# Sheet1.net
KiCad netlist of a schematic drawn in Altium Designer
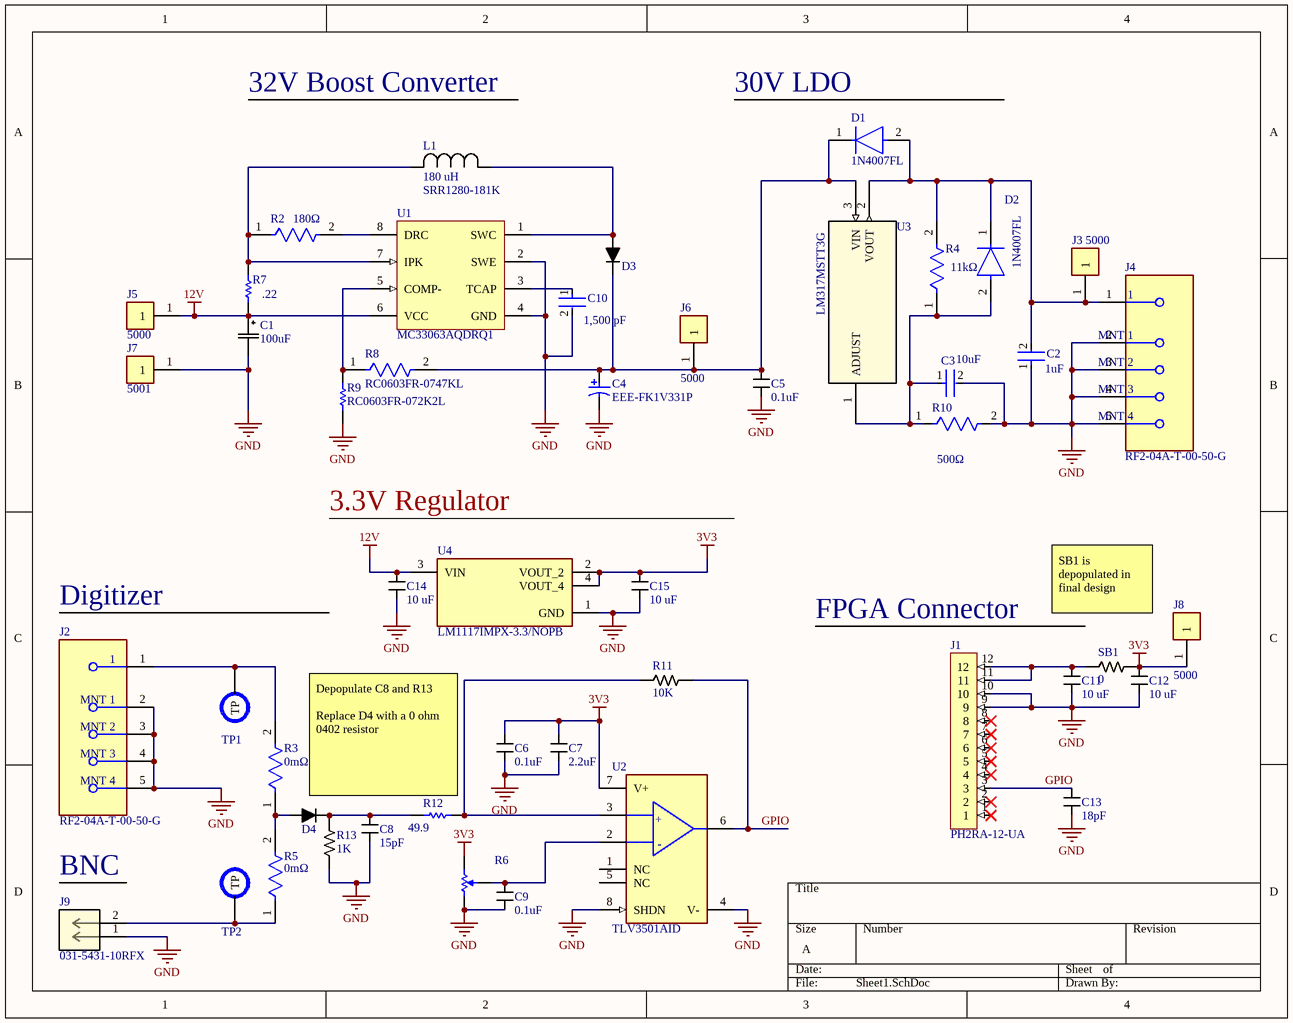
[diagram p0: Sheet1.SchDoc]

(export (version "E")
  (design (tool "Eeschema 10.0.6"))
  (components
    (comp (ref "C1")
      (value "100uF")
      (footprint "PCAP_8x5.4-ELECT_NCA")
      (description "100 µF 35 V Aluminum Electrolytic Capacitors Radial, Can - SMD 1000 Hrs")
      (fields
        (field (name "MANUFACTURER_PART_NUMBER") "UCB1V0R1MCL1GS")
        (field (name "Comment") "100uF electrolytic 35 V")
        (field (name "COPYRIGHT") "Copyright (C) 2022 Ultra Librarian. All rights reserved.")
        (field (name "MADE BY") "Tyson Nguyen")
      )
      (libsource (lib "Capacitors") (part "CAP ALUM 100UF 20% 35V SMD"))
    )
    (comp (ref "C2")
      (value "UMK107BJ105KA-T")
      (footprint "FP-0603-L_1_6_0_1-W_0_8_0-IPC_A")
      (description "None")
      (fields (field (name "TOLERANCE") "10%") (field (name "CAPACITANCE") "1uF"))
      (libsource (lib "Altium Content Vault") (part "02cd4be3c70576c341d710602a673aa"))
    )
    (comp (ref "C3")
      (value "GRM188R6YA106MA73D")
      (footprint "FP-GRM188-0_2-IPC_C")
      (description "Chip Multilayer Ceramic Capacitors for General Purpose, 0603, 10uF, X5R, 15%, 20%, 35V")
      (fields (field (name "CAPACITANCE") "10uF") (field (name "TOLERANCE") "20%"))
      (libsource (lib "Altium Content Vault") (part "11868f565c42a9108669ba33697ecf6"))
    )
    (comp (ref "C4")
      (value "EEE-FK1V331P")
      (footprint "PNSC-EEE-FK1V331P_L")
      (description "Aluminum Electrolytic Capacitor, 330 uF, 35 V, -55 to 105 degC, 2-Pin CAPAE, RoHS, Tape and Reel")
      (fields (field (name "MANUFACTURER") "Panasonic"))
      (libsource (lib "Altium Content Vault") (part "CAP-P-2"))
    )
    (comp (ref "C5")
      (value "0.1uF")
      (footprint "CAPACITOR_0805")
      (description "Cap 100nF 50V +/-10%\r\nCeramic 0805")
      (fields
        (field (name "TOLERANCE") "+/- 10%")
        (field (name "VOLTAGE") "50V")
        (field (name "MADE BY") "Robert Pafford")
      )
      (libsource (lib "Capacitors") (part "CAPACITOR_0.1uF_0805"))
    )
    (comp (ref "C6")
      (value "0.1uF")
      (footprint "CAPACITOR_0603")
      (description "Cap 100nF 25V +/-10%\r\nCeramic 0603")
      (fields
        (field (name "TOLERANCE") "+/- 10%")
        (field (name "VOLTAGE") "6.3V")
        (field (name "MADE BY") "Flip B")
      )
      (libsource (lib "Capacitors") (part "CAPACITOR_0.1uF_0603_25V"))
    )
    (comp (ref "C7")
      (value "2.2uF")
      (footprint "CAPACITOR_0402")
      (description "Cap 2.2uF 35V +/-10%\r\nCeramic 0402")
      (fields
        (field (name "TOLERANCE") "+/- 10%")
        (field (name "VOLTAGE") "35V")
        (field (name "MADE BY") "Flip B")
      )
      (libsource (lib "Capacitors") (part "CAPACITOR_2.2uF_0402"))
    )
    (comp (ref "C8")
      (value "15pF")
      (footprint "CAPACITOR_0402")
      (description "CAP CER 15PF 50V C0G/NP0 0402")
      (fields
        (field (name "TOLERANCE") "+/- 5%")
        (field (name "VOLTAGE") "50V")
        (field (name "MADE BY") "Robert Pafford")
      )
      (libsource (lib "Capacitors") (part "CAPACITOR_0.000015uF_0402"))
    )
    (comp (ref "C9")
      (value "0.1uF")
      (footprint "CAPACITOR_0603")
      (description "Cap 100nF 25V +/-10%\r\nCeramic 0603")
      (fields
        (field (name "TOLERANCE") "+/- 10%")
        (field (name "VOLTAGE") "6.3V")
        (field (name "MADE BY") "Flip B")
      )
      (libsource (lib "Capacitors") (part "CAPACITOR_0.1uF_0603_25V"))
    )
    (comp (ref "C10")
      (value "1,500 pF")
      (footprint "FP-C0603C-CF-MFG")
      (description "CAP CER 1500PF 100V NP0 0603")
      (fields (field (name "MANUFACTURER") "KEMET") (field (name "TOLERANCE") "0.01"))
      (libsource (lib "Altium Content Vault") (part "b4654b650e69147ec39a6b967a45e02"))
    )
    (comp (ref "C11")
      (value "10uF Ceramic 6.3V")
      (footprint "CAPACITOR_0603")
      (description "Cap 10uF 6.3V +/-20%\r\nCeramic 0603")
      (fields
        (field (name "TOLERANCE") "+/- 20%")
        (field (name "VOLTAGE") "6.3V")
        (field (name "VALUE (UF)") "10 uF")
        (field (name "MADE BY") "Flip B")
      )
      (libsource (lib "Capacitors") (part "CAPACITOR_10uF_0603"))
    )
    (comp (ref "C12")
      (value "10uF Ceramic 6.3V")
      (footprint "CAPACITOR_0603")
      (description "Cap 10uF 6.3V +/-20%\r\nCeramic 0603")
      (fields
        (field (name "TOLERANCE") "+/- 20%")
        (field (name "VOLTAGE") "6.3V")
        (field (name "VALUE (UF)") "10 uF")
        (field (name "MADE BY") "Flip B")
      )
      (libsource (lib "Capacitors") (part "CAPACITOR_10uF_0603"))
    )
    (comp (ref "C13")
      (value "18pF")
      (footprint "CAPACITOR_0603")
      (description "Cap 18pF 50V +/-5%\r\nCeramic 0603")
      (fields
        (field (name "TOLERANCE") "+/- 5%")
        (field (name "VOLTAGE") "50V")
        (field (name "MADE BY") "Flip B")
      )
      (libsource (lib "Capacitors") (part "CAPACITOR_0.000018uF_0603"))
    )
    (comp (ref "C14")
      (value "10uF Ceramic 6.3V")
      (footprint "CAPACITOR_0603")
      (description "Cap 10uF 6.3V +/-20%\r\nCeramic 0603")
      (fields
        (field (name "TOLERANCE") "+/- 20%")
        (field (name "VOLTAGE") "6.3V")
        (field (name "VALUE (UF)") "10 uF")
        (field (name "MADE BY") "Flip B")
      )
      (libsource (lib "Capacitors") (part "CAPACITOR_10uF_0603"))
    )
    (comp (ref "C15")
      (value "10uF Ceramic 6.3V")
      (footprint "CAPACITOR_0603")
      (description "Cap 10uF 6.3V +/-20%\r\nCeramic 0603")
      (fields
        (field (name "TOLERANCE") "+/- 20%")
        (field (name "VOLTAGE") "6.3V")
        (field (name "VALUE (UF)") "10 uF")
        (field (name "MADE BY") "Flip B")
      )
      (libsource (lib "Capacitors") (part "CAPACITOR_10uF_0603"))
    )
    (comp (ref "D1")
      (value "1N4007FL")
      (footprint "FP-1N4007FL-MFG")
      (description "1N4007FL Diode Gen Purp 1KV 1A SOD123FL")
      (libsource (lib "Altium Content Vault") (part "d7152d700b627762746794eb795d46e"))
    )
    (comp (ref "D2")
      (value "1N4007FL")
      (footprint "FP-1N4007FL-MFG")
      (description "1N4007FL Diode Gen Purp 1KV 1A SOD123FL")
      (libsource (lib "Altium Content Vault") (part "d7152d700b627762746794eb795d46e"))
    )
    (comp (ref "D3")
      (value "STPS140Z")
      (footprint "SOD-123")
      (description "DIODE SCHOTTKY 40V 1A SOD123")
      (libsource (lib "Diodes") (part "STPS140Z"))
    )
    (comp (ref "D4")
      (value "BAR9002ELE6327XTMA1")
      (footprint "DIODE_0402")
      (description "RF Diode PIN - Single 80V 100 mA 250 mW PG-TSLP-2-19")
      (libsource (lib "Diodes") (part "RF Diode 80V 100mA"))
    )
    (comp (ref "J1")
      (value "PH2RA-12-UA")
      (footprint "PH2RA-12-UA-Footprint-1")
      (description "Conn Unshrouded Header HDR 12 POS 2.54mm Solder RA Top Entry Thru-Hole Bag")
      (libsource (lib "XCOM_capstone") (part "PH2RA-12-UA-Symbol-1"))
    )
    (comp (ref "J2")
      (value "RF2-04A-T-00-50-G")
      (footprint "FP-RF2-04A-T-00-50-G-MFG")
      (description "CONN SMA JACK STR 50 OHM PCB")
      (libsource (lib "Altium Content Vault") (part "c65b8a639cdaef1819ea20b5466f8fa"))
    )
    (comp (ref "J3")
      (value "5000")
      (footprint "FP-5000-MFG")
      (description "Cable Wrap, 1/2 Inch, Polyethylene, Natural, 50 Ft, Spirap Series")
      (libsource (lib "XCOM_capstone") (part "1e4615820a309e3ce90f9e6d957b7fa"))
    )
    (comp (ref "J4")
      (value "RF2-04A-T-00-50-G")
      (footprint "FP-RF2-04A-T-00-50-G-MFG")
      (description "CONN SMA JACK STR 50 OHM PCB")
      (libsource (lib "") (part "c65b8a639cdaef1819ea20b5466f8fa_1"))
    )
    (comp (ref "J5")
      (value "5000")
      (footprint "FP-5000-MFG")
      (description "Cable Wrap, 1/2 Inch, Polyethylene, Natural, 50 Ft, Spirap Series")
      (libsource (lib "") (part "1e4615820a309e3ce90f9e6d957b7fa_1"))
    )
    (comp (ref "J6")
      (value "5000")
      (footprint "FP-5000-MFG")
      (description "Cable Wrap, 1/2 Inch, Polyethylene, Natural, 50 Ft, Spirap Series")
      (libsource (lib "XCOM_capstone") (part "1e4615820a309e3ce90f9e6d957b7fa"))
    )
    (comp (ref "J7")
      (value "5001")
      (footprint "FP-5001-MFG")
      (description "Test Point, Mini, Thm, Pc, .300 L, .100 Od, Heat Resistant Nylon 46, Black")
      (libsource (lib "") (part "1e4615820a309e3ce90f9e6d957b7fa_1"))
    )
    (comp (ref "J8")
      (value "5000")
      (footprint "FP-5000-MFG")
      (description "Cable Wrap, 1/2 Inch, Polyethylene, Natural, 50 Ft, Spirap Series")
      (libsource (lib "XCOM_capstone") (part "1e4615820a309e3ce90f9e6d957b7fa"))
    )
    (comp (ref "J9")
      (value "031-5431-10RFX")
      (footprint "031-5431-10RFX-Footprint-1")
      (description "RF BNC Connector, Female, Panel Mount, Board And Panel Mount, Solder Terminal, Jack")
      (libsource (lib "XCOM_capstone") (part "031-5431-10RFX-Symbol-1"))
    )
    (comp (ref "L1")
      (value "SRR1280-181K")
      (footprint "SRR1280")
      (description "FIXED IND 180UH 1.75A 300 MOHM")
      (fields (field (name "ALTIUM_VALUE") "180 uH"))
      (libsource (lib "Inductors") (part "SRR1280-181K"))
    )
    (comp (ref "R2")
      (value "CRGCQ0603F180R")
      (footprint "FP-CRGCQ0603-IPC_C")
      (description "CRGCQ 0603 180R 1%")
      (fields
        (field (name "OCTOPART") "https://octopart.com/crgcq0603f180r-te+connectivity-91018047")
        (field (name "TOLERANCE") "0.01")
        (field (name "RESISTANCE") "180Ω")
      )
      (libsource (lib "Altium Content Vault") (part "1029c3af85768c4190bb7ad29bc67b5"))
    )
    (comp (ref "R3")
      (value "RMCF0603ZT0R00")
      (footprint "FP-RMCF0603-MFG")
      (description "RES 0 OHM JUMPER 1/10W 0603")
      (fields
        (field (name "OCTOPART") "https://octopart.com/rmcf0603zt0r00-stackpole+electronics-19213618")
        (field (name "MANUFACTURER") "Stackpole")
        (field (name "RESISTANCE") "0mΩ")
      )
      (libsource (lib "Altium Content Vault") (part "1029c3af85768c4190bb7ad29bc67b5"))
    )
    (comp (ref "R4")
      (value "ERA-2AEB113X")
      (footprint "FP-ERA2A-MFG")
      (fields (field (name "RESISTANCE") "11kΩ") (field (name "TOLERANCE") "0.1%"))
      (libsource (lib "Altium Content Vault") (part "1029c3af85768c4190bb7ad29bc67b5"))
    )
    (comp (ref "R5")
      (value "RMCF0603ZT0R00")
      (footprint "FP-RMCF0603-MFG")
      (description "RES 0 OHM JUMPER 1/10W 0603")
      (fields
        (field (name "OCTOPART") "https://octopart.com/rmcf0603zt0r00-stackpole+electronics-19213618")
        (field (name "MANUFACTURER") "Stackpole")
        (field (name "RESISTANCE") "0mΩ")
      )
      (libsource (lib "Altium Content Vault") (part "1029c3af85768c4190bb7ad29bc67b5"))
    )
    (comp (ref "R6")
      (value "TC33X-2-103E")
      (footprint "BOUR-TC33X-2_V")
      (description "Trimming Potentiometer, 10000 Ohm, -40 to 100 degC, 3-Pin SMD, RoHS, Tape and Reel")
      (fields (field (name "TOLERANCE") "25%") (field (name "POWER") "100mW"))
      (libsource (lib "XCOM_capstone") (part "RES-ADJ-3_A"))
    )
    (comp (ref "R7")
      (value ".22")
      (footprint "RESC1608X55X30NL15T15")
      (fields (field (name "PART NUMBER") "ERJ-3RQFR22V") (field (name "MANUFACTURER") "Panasonic"))
      (libsource (lib "Altium Content Vault") (part "RES"))
    )
    (comp (ref "R8")
      (value "RC0603FR-0747KL")
      (footprint "FP-RC0603FR-0747KL-MFG")
      (description "RES SMD 47K OHM 1% 1/10W 0603")
      (fields (field (name "TOLERANCE") "1%"))
      (libsource (lib "Altium Content Vault") (part "1029c3af85768c4190bb7ad29bc67b5"))
    )
    (comp (ref "R9")
      (value "RC0603FR-072K2L")
      (footprint "RESC1608X55X25LL10T15")
      (fields (field (name "TOLERANCE") "1%") (field (name "MANUFACTURER") "Yageo"))
      (libsource (lib "Altium Content Vault") (part "RES-2"))
    )
    (comp (ref "R10")
      (value "RT0603BRC07500RL")
      (footprint "RESC16080X45_RT0603-0_55_MFG")
      (description "Fixed Resistor, Thin Film, 0.1W, 500ohm, 75V, 0.1% +/-Tol, 15ppm/Cel, Surface Mount, 0603")
      (fields (field (name "TOLERANCE") "0.1%"))
      (libsource (lib "Altium Content Vault") (part "beb0a2e81d78bb8429d162089e89c6a"))
    )
    (comp (ref "R11")
      (value "10k Ohm 1% 1/16W")
      (footprint "RESISTOR_0402")
      (description "RES 10k OHM 1% 1/16W 0402")
      (fields
        (field (name "TOLERANCE") "+/- 1%")
        (field (name "VALUE  (OHMS)") "10K")
        (field (name "MADE BY") "Robert Pafford")
      )
      (libsource (lib "Resistors") (part "RESISTOR_10K_0402"))
    )
    (comp (ref "R12")
      (value "49.9")
      (footprint "RESC1005X40X25LL05T10")
      (fields (field (name "MANUFACTURER") "Yageo / Phycomp") (field (name "PART NUMBER") "RC0402FR-0749R9L"))
      (libsource (lib "Altium Content Vault") (part "RES"))
    )
    (comp (ref "R13")
      (value "1k Ohm 5% 1/8W")
      (footprint "RESISTOR_0603")
      (description "RES 1k OHM 5% 1/8W 0603")
      (fields
        (field (name "TOLERANCE") "+/- 5%")
        (field (name "VALUE  (OHMS)") "1K")
        (field (name "MADE BY") "Robert Pafford")
      )
      (libsource (lib "Resistors") (part "RESISTOR_1K_0603"))
    )
    (comp (ref "SB1")
      (value "0")
      (footprint "RESISTOR_1206")
      (description "JUMPER 0OHM 1206")
      (fields (field (name "Comment") "JUMPER_0_1206"))
      (libsource (lib "Resistors") (part "JUMPER_0_1206"))
    )
    (comp (ref "TP1")
      (value "PCB Test Point")
      (footprint "TESTPOINT_1.2MM")
      (fields (field (name "MADE BY") "Robert Pafford"))
      (libsource (lib "Connectors") (part "TESTPOINT"))
    )
    (comp (ref "TP2")
      (value "PCB Test Point")
      (footprint "TESTPOINT_1.2MM")
      (fields (field (name "MADE BY") "Robert Pafford"))
      (libsource (lib "Connectors") (part "TESTPOINT"))
    )
    (comp (ref "U1")
      (value "MC33063AQDRQ1")
      (footprint "D0008A_L")
      (fields (field (name "MANUFACTURER") "Texas Instruments"))
      (libsource (lib "Altium Content Vault") (part "TI-MC33063A-Q1D8"))
    )
    (comp (ref "U2")
      (value "TLV3501AID")
      (footprint "FP-D0008A-IPC_C")
      (description "IC COMPARATOR 4.5NS R-R HS 8SOIC")
      (libsource (lib "Altium Content Vault") (part "734816f6191e347792cdd10dde819a7"))
    )
    (comp (ref "U3")
      (value "LM317MSTT3G")
      (footprint "SOT223-3")
      (description "Linear Voltage Regulator IC Positive Adjustable 1 Output 500mA SOT-223 (TO-261)")
      (libsource (lib "Integrated Circuits") (part "LM317MSTT3G"))
    )
    (comp (ref "U4")
      (value "LM1117IMPX-3.3/NOPB")
      (footprint "SOT-223-4")
      (description "800-mA 15-V linear voltage regulator 4-SOT-223 -40 to 125")
      (fields (field (name "MF") "Texas Instruments"))
      (libsource (lib "Integrated Circuits") (part "LM1117IMPX-3.3/NOPB"))
    )
  )
  (nets
    (net (code "1") (name "/GPIO") (class "Default")
      (node (ref "C13") (pin "1") (pinfunction "1_1") (pintype "passive"))
      (node (ref "J1") (pin "3") (pinfunction "3_3") (pintype "input"))
      (node (ref "R11") (pin "1") (pinfunction "1_1") (pintype "passive"))
      (node (ref "U2") (pin "6") (pinfunction "OUT_6") (pintype "passive"))
    )
    (net (code "2") (name "3V3") (class "Default")
      (node (ref "C12") (pin "1") (pinfunction "1_1") (pintype "passive"))
      (node (ref "C15") (pin "1") (pinfunction "1_1") (pintype "passive"))
      (node (ref "C6") (pin "1") (pinfunction "1_1") (pintype "passive"))
      (node (ref "C7") (pin "1") (pinfunction "1_1") (pintype "passive"))
      (node (ref "J8") (pin "1") (pinfunction "1_1") (pintype "passive"))
      (node (ref "R6") (pin "3") (pinfunction "3_3") (pintype "passive"))
      (node (ref "SB1") (pin "1") (pinfunction "1_1") (pintype "passive"))
      (node (ref "U2") (pin "7") (pinfunction "V+_7") (pintype "power_in"))
      (node (ref "U4") (pin "2") (pinfunction "VOUT_2_2") (pintype "power_in"))
      (node (ref "U4") (pin "4") (pinfunction "VOUT_4_4") (pintype "power_in"))
    )
    (net (code "3") (name "12V") (class "Default")
      (node (ref "C1") (pin "1") (pinfunction "1_1") (pintype "passive"))
      (node (ref "C14") (pin "1") (pinfunction "1_1") (pintype "passive"))
      (node (ref "J5") (pin "1") (pinfunction "1_1") (pintype "passive"))
      (node (ref "R7") (pin "1") (pinfunction "1_1") (pintype "passive"))
      (node (ref "U1") (pin "6") (pinfunction "VCC_6") (pintype "power_in"))
      (node (ref "U4") (pin "3") (pinfunction "VIN_3") (pintype "power_in"))
    )
    (net (code "4") (name "GND") (class "Default")
      (node (ref "C1") (pin "2") (pinfunction "2_2") (pintype "passive"))
      (node (ref "C10") (pin "2") (pinfunction "2_2") (pintype "passive"))
      (node (ref "C11") (pin "2") (pinfunction "2_2") (pintype "passive"))
      (node (ref "C12") (pin "2") (pinfunction "2_2") (pintype "passive"))
      (node (ref "C13") (pin "2") (pinfunction "2_2") (pintype "passive"))
      (node (ref "C14") (pin "2") (pinfunction "2_2") (pintype "passive"))
      (node (ref "C15") (pin "2") (pinfunction "2_2") (pintype "passive"))
      (node (ref "C2") (pin "1") (pinfunction "1_1") (pintype "passive"))
      (node (ref "C3") (pin "2") (pinfunction "2_2") (pintype "passive"))
      (node (ref "C4") (pin "2") (pinfunction "2_2") (pintype "passive"))
      (node (ref "C5") (pin "2") (pinfunction "2_2") (pintype "passive"))
      (node (ref "C6") (pin "2") (pinfunction "2_2") (pintype "passive"))
      (node (ref "C7") (pin "2") (pinfunction "2_2") (pintype "passive"))
      (node (ref "C8") (pin "2") (pinfunction "2_2") (pintype "passive"))
      (node (ref "C9") (pin "2") (pinfunction "2_2") (pintype "passive"))
      (node (ref "J1") (pin "10") (pinfunction "10_10") (pintype "input"))
      (node (ref "J1") (pin "9") (pinfunction "9_9") (pintype "input"))
      (node (ref "J2") (pin "2") (pinfunction "MNT_1_2") (pintype "passive"))
      (node (ref "J2") (pin "3") (pinfunction "MNT_2_3") (pintype "passive"))
      (node (ref "J2") (pin "4") (pinfunction "MNT_3_4") (pintype "passive"))
      (node (ref "J2") (pin "5") (pinfunction "MNT_4_5") (pintype "passive"))
      (node (ref "J4") (pin "2") (pinfunction "MNT_1_2") (pintype "passive"))
      (node (ref "J4") (pin "3") (pinfunction "MNT_2_3") (pintype "passive"))
      (node (ref "J4") (pin "4") (pinfunction "MNT_3_4") (pintype "passive"))
      (node (ref "J4") (pin "5") (pinfunction "MNT_4_5") (pintype "passive"))
      (node (ref "J7") (pin "1") (pinfunction "1_1") (pintype "passive"))
      (node (ref "J9") (pin "1") (pinfunction "1_1") (pintype "passive"))
      (node (ref "R10") (pin "2") (pinfunction "2_2") (pintype "passive"))
      (node (ref "R13") (pin "2") (pinfunction "2_2") (pintype "passive"))
      (node (ref "R6") (pin "1") (pinfunction "1_1") (pintype "passive"))
      (node (ref "R9") (pin "1") (pinfunction "1_1") (pintype "passive"))
      (node (ref "U1") (pin "2") (pinfunction "SWE_2") (pintype "open_emitter"))
      (node (ref "U1") (pin "4") (pinfunction "GND_4") (pintype "power_in"))
      (node (ref "U2") (pin "4") (pinfunction "V-_4") (pintype "power_in"))
      (node (ref "U2") (pin "8") (pinfunction "SHDN_8") (pintype "input"))
      (node (ref "U4") (pin "1") (pinfunction "GND_1") (pintype "power_in"))
    )
    (net (code "5") (name "Net-(C8-Pad1)") (class "Default")
      (node (ref "C8") (pin "1") (pinfunction "1_1") (pintype "passive"))
      (node (ref "D4") (pin "2") (pinfunction "2_2") (pintype "passive"))
      (node (ref "R12") (pin "1") (pinfunction "1_1") (pintype "passive"))
      (node (ref "R13") (pin "1") (pinfunction "1_1") (pintype "passive"))
    )
    (net (code "6") (name "Net-(C11-Pad1)") (class "Default")
      (node (ref "C11") (pin "1") (pinfunction "1_1") (pintype "passive"))
      (node (ref "J1") (pin "11") (pinfunction "11_11") (pintype "input"))
      (node (ref "J1") (pin "12") (pinfunction "12_12") (pintype "input"))
      (node (ref "SB1") (pin "2") (pinfunction "2_2") (pintype "passive"))
    )
    (net (code "7") (name "Net-(D1-A)") (class "Default")
      (node (ref "C2") (pin "2") (pinfunction "2_2") (pintype "passive"))
      (node (ref "D1") (pin "2") (pinfunction "A_2") (pintype "passive"))
      (node (ref "D2") (pin "1") (pinfunction "C_1") (pintype "passive"))
      (node (ref "J3") (pin "1") (pinfunction "1_1") (pintype "passive"))
      (node (ref "J4") (pin "1") (pinfunction "1_1") (pintype "passive"))
      (node (ref "R4") (pin "2") (pinfunction "2_2") (pintype "passive"))
      (node (ref "U3") (pin "2") (pinfunction "VOUT_2") (pintype "output"))
    )
    (net (code "8") (name "Net-(D1-C)") (class "Default")
      (node (ref "C4") (pin "1") (pinfunction "1_1") (pintype "passive"))
      (node (ref "C5") (pin "1") (pinfunction "1_1") (pintype "passive"))
      (node (ref "D1") (pin "1") (pinfunction "C_1") (pintype "passive"))
      (node (ref "D3") (pin "2") (pinfunction "2_2") (pintype "passive"))
      (node (ref "J6") (pin "1") (pinfunction "1_1") (pintype "passive"))
      (node (ref "R8") (pin "2") (pinfunction "2_2") (pintype "passive"))
      (node (ref "U3") (pin "3") (pinfunction "VIN_3") (pintype "input"))
    )
    (net (code "9") (name "Net-(D2-A)") (class "Default")
      (node (ref "C3") (pin "1") (pinfunction "1_1") (pintype "passive"))
      (node (ref "D2") (pin "2") (pinfunction "A_2") (pintype "passive"))
      (node (ref "R10") (pin "1") (pinfunction "1_1") (pintype "passive"))
      (node (ref "R4") (pin "1") (pinfunction "1_1") (pintype "passive"))
      (node (ref "U3") (pin "1") (pinfunction "ADJUST_1") (pintype "passive"))
    )
    (net (code "10") (name "Net-(D4-Pad1)") (class "Default")
      (node (ref "D4") (pin "1") (pinfunction "1_1") (pintype "passive"))
      (node (ref "R3") (pin "1") (pinfunction "1_1") (pintype "passive"))
      (node (ref "R5") (pin "2") (pinfunction "2_2") (pintype "passive"))
    )
    (net (code "11") (name "Net-(J2-Pad1)") (class "Default")
      (node (ref "J2") (pin "1") (pinfunction "1_1") (pintype "passive"))
      (node (ref "R3") (pin "2") (pinfunction "2_2") (pintype "passive"))
      (node (ref "TP1") (pin "TP") (pinfunction "TP_TP") (pintype "passive"))
    )
    (net (code "12") (name "Net-(J9-Pad2)") (class "Default")
      (node (ref "J9") (pin "2") (pinfunction "2_2") (pintype "passive"))
      (node (ref "R5") (pin "1") (pinfunction "1_1") (pintype "passive"))
      (node (ref "TP2") (pin "TP") (pinfunction "TP_TP") (pintype "passive"))
    )
    (net (code "13") (name "Net-(U1-COMP-)") (class "Default")
      (node (ref "R8") (pin "1") (pinfunction "1_1") (pintype "passive"))
      (node (ref "R9") (pin "2") (pinfunction "2_2") (pintype "passive"))
      (node (ref "U1") (pin "5") (pinfunction "COMP-_5") (pintype "input"))
    )
    (net (code "14") (name "Net-(U1-DRC)") (class "Default")
      (node (ref "R2") (pin "2") (pinfunction "2_2") (pintype "passive"))
      (node (ref "U1") (pin "8") (pinfunction "DRC_8") (pintype "open_collector"))
    )
    (net (code "15") (name "Net-(U1-IPK)") (class "Default")
      (node (ref "L1") (pin "2") (pinfunction "2_2") (pintype "passive"))
      (node (ref "R2") (pin "1") (pinfunction "1_1") (pintype "passive"))
      (node (ref "R7") (pin "2") (pinfunction "2_2") (pintype "passive"))
      (node (ref "U1") (pin "7") (pinfunction "IPK_7") (pintype "input"))
    )
    (net (code "16") (name "Net-(U1-SWC)") (class "Default")
      (node (ref "D3") (pin "1") (pinfunction "1_1") (pintype "passive"))
      (node (ref "L1") (pin "1") (pinfunction "1_1") (pintype "passive"))
      (node (ref "U1") (pin "1") (pinfunction "SWC_1") (pintype "open_collector"))
    )
    (net (code "17") (name "Net-(U1-TCAP)") (class "Default")
      (node (ref "C10") (pin "1") (pinfunction "1_1") (pintype "passive"))
      (node (ref "U1") (pin "3") (pinfunction "TCAP_3") (pintype "passive"))
    )
    (net (code "18") (name "Net-(U2-+IN)") (class "Default")
      (node (ref "R11") (pin "2") (pinfunction "2_2") (pintype "passive"))
      (node (ref "R12") (pin "2") (pinfunction "2_2") (pintype "passive"))
      (node (ref "U2") (pin "3") (pinfunction "+IN_3") (pintype "tri_state"))
    )
    (net (code "19") (name "Net-(U2--IN)") (class "Default")
      (node (ref "C9") (pin "1") (pinfunction "1_1") (pintype "passive"))
      (node (ref "R6") (pin "2") (pinfunction "2_2") (pintype "passive"))
      (node (ref "U2") (pin "2") (pinfunction "-IN_2") (pintype "tri_state"))
    )
    (net (code "20") (name "unconnected-(J1-Pad1)") (class "Default")
      (node (ref "J1") (pin "1") (pinfunction "1_1") (pintype "input+no_connect"))
    )
    (net (code "21") (name "unconnected-(J1-Pad2)") (class "Default")
      (node (ref "J1") (pin "2") (pinfunction "2_2") (pintype "input+no_connect"))
    )
    (net (code "22") (name "unconnected-(J1-Pad4)") (class "Default")
      (node (ref "J1") (pin "4") (pinfunction "4_4") (pintype "input+no_connect"))
    )
    (net (code "23") (name "unconnected-(J1-Pad5)") (class "Default")
      (node (ref "J1") (pin "5") (pinfunction "5_5") (pintype "input+no_connect"))
    )
    (net (code "24") (name "unconnected-(J1-Pad6)") (class "Default")
      (node (ref "J1") (pin "6") (pinfunction "6_6") (pintype "input+no_connect"))
    )
    (net (code "25") (name "unconnected-(J1-Pad7)") (class "Default")
      (node (ref "J1") (pin "7") (pinfunction "7_7") (pintype "input+no_connect"))
    )
    (net (code "26") (name "unconnected-(J1-Pad8)") (class "Default")
      (node (ref "J1") (pin "8") (pinfunction "8_8") (pintype "input+no_connect"))
    )
    (net (code "27") (name "unconnected-(U2-NC-Pad1)") (class "Default")
      (node (ref "U2") (pin "1") (pinfunction "NC_1") (pintype "passive"))
    )
    (net (code "28") (name "unconnected-(U2-NC-Pad5)") (class "Default")
      (node (ref "U2") (pin "5") (pinfunction "NC_5") (pintype "passive"))
    )
  )
)
